# Output_Buffer.net
KiCad netlist of a schematic drawn in Altium Designer
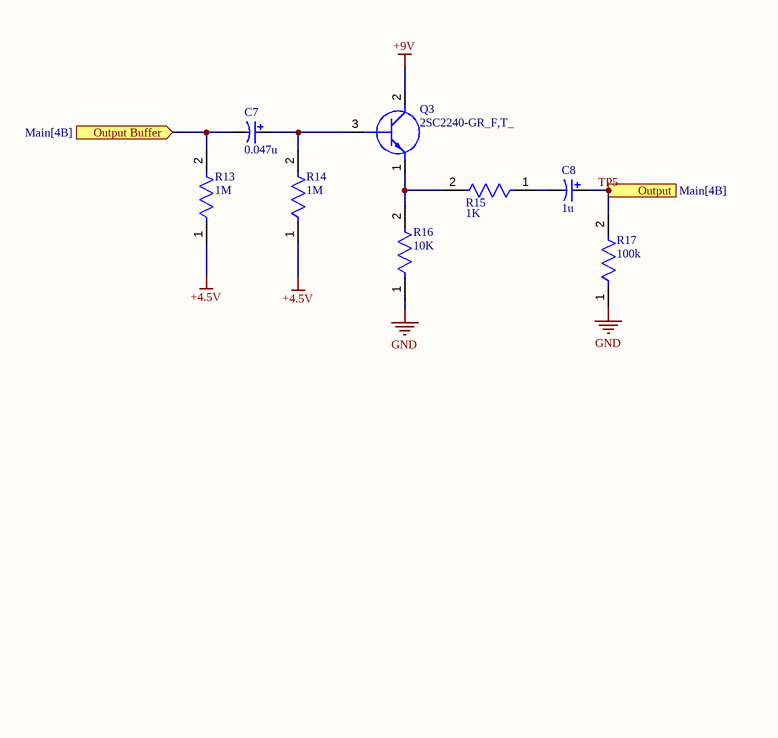
[diagram p0: Output_Buffer.SchDoc]

(export (version "E")
  (design (tool "Eeschema 10.0.6"))
  (components
    (comp (ref "C7")
      (value "0.047u")
      (footprint "CAPPR55-200-1100X500X1200")
      (description "Aluminum Electrolytic Capacitor, 22 uF, +/- 20%, 50 V, -40 to 85 degC, 2-Pin THD, RoHS, Bulk")
      (fields (field (name "VOLTAGE") "50V") (field (name "MANUFACTURER") "Panasonic"))
      (libsource (lib "Altium Content Vault") (part "CAP-P-2"))
    )
    (comp (ref "C8")
      (value "1u")
      (footprint "CAPPR55-200-1100X500X1200")
      (description "Aluminum Electrolytic Capacitor, 22 uF, +/- 20%, 50 V, -40 to 85 degC, 2-Pin THD, RoHS, Bulk")
      (fields (field (name "VOLTAGE") "50V") (field (name "MANUFACTURER") "Panasonic"))
      (libsource (lib "Altium Content Vault") (part "CAP-P-2"))
    )
    (comp (ref "Q3")
      (value "2SC2240-GR_F,T_")
      (footprint "SamacSys:SSM3K7002CFULF")
      (description "Transistor BJT NPN")
      (fields
        (field (name "MANUFACTURER_PART_NUMBER") "2SC2240-GR(F,T)")
        (field (name "MOUSER PART NUMBER") "757-2SC2240-GRFT")
      )
      (libsource (lib "*") (part "2SC2240-GR_F,T_"))
    )
    (comp (ref "R13")
      (value "1M")
      (footprint "FP-MRS1600-MFG")
      (description "RES 20K OHM 0.4W 1% AXIAL")
      (fields (field (name "TOLERANCE") "1%"))
      (libsource (lib "Altium Content Vault") (part "1029c3af85768c4190bb7ad29bc67b5"))
    )
    (comp (ref "R14")
      (value "1M")
      (footprint "FP-MRS1600-MFG")
      (description "RES 20K OHM 0.4W 1% AXIAL")
      (fields (field (name "TOLERANCE") "1%"))
      (libsource (lib "Altium Content Vault") (part "1029c3af85768c4190bb7ad29bc67b5"))
    )
    (comp (ref "R15")
      (value "1K")
      (footprint "FP-MRS1600-MFG")
      (description "RES 20K OHM 0.4W 1% AXIAL")
      (fields (field (name "TOLERANCE") "1%"))
      (libsource (lib "Altium Content Vault") (part "1029c3af85768c4190bb7ad29bc67b5"))
    )
    (comp (ref "R16")
      (value "10K")
      (footprint "FP-MRS1600-MFG")
      (description "RES 20K OHM 0.4W 1% AXIAL")
      (fields (field (name "TOLERANCE") "1%"))
      (libsource (lib "Altium Content Vault") (part "1029c3af85768c4190bb7ad29bc67b5"))
    )
    (comp (ref "R17")
      (value "100k")
      (footprint "FP-MRS1600-MFG")
      (description "RES 20K OHM 0.4W 1% AXIAL")
      (fields (field (name "TOLERANCE") "1%"))
      (libsource (lib "Altium Content Vault") (part "1029c3af85768c4190bb7ad29bc67b5"))
    )
  )
  (nets
    (net (code "1") (name "+4.5V") (class "Default")
      (node (ref "R13") (pin "1") (pinfunction "1_1") (pintype "passive"))
      (node (ref "R14") (pin "1") (pinfunction "1_1") (pintype "passive"))
    )
    (net (code "2") (name "+9V") (class "Default")
      (node (ref "Q3") (pin "2") (pinfunction "C_2") (pintype "passive"))
    )
    (net (code "3") (name "/Output Buffer") (class "Default")
      (node (ref "C7") (pin "2") (pinfunction "2_2") (pintype "passive"))
      (node (ref "R13") (pin "2") (pinfunction "2_2") (pintype "passive"))
    )
    (net (code "4") (name "/TP5") (class "Default")
      (node (ref "C8") (pin "1") (pinfunction "1_1") (pintype "passive"))
      (node (ref "R17") (pin "2") (pinfunction "2_2") (pintype "passive"))
    )
    (net (code "5") (name "GND") (class "Default")
      (node (ref "R16") (pin "1") (pinfunction "1_1") (pintype "passive"))
      (node (ref "R17") (pin "1") (pinfunction "1_1") (pintype "passive"))
    )
    (net (code "6") (name "Net-(C8-Pad2)") (class "Default")
      (node (ref "C8") (pin "2") (pinfunction "2_2") (pintype "passive"))
      (node (ref "R15") (pin "1") (pinfunction "1_1") (pintype "passive"))
    )
    (net (code "7") (name "Net-(Q3-B)") (class "Default")
      (node (ref "C7") (pin "1") (pinfunction "1_1") (pintype "passive"))
      (node (ref "Q3") (pin "3") (pinfunction "B_3") (pintype "passive"))
      (node (ref "R14") (pin "2") (pinfunction "2_2") (pintype "passive"))
    )
    (net (code "8") (name "Net-(Q3-E)") (class "Default")
      (node (ref "Q3") (pin "1") (pinfunction "E_1") (pintype "passive"))
      (node (ref "R15") (pin "2") (pinfunction "2_2") (pintype "passive"))
      (node (ref "R16") (pin "2") (pinfunction "2_2") (pintype "passive"))
    )
  )
)
